# TEMPSENS.net
KiCad netlist of a schematic drawn in Altium Designer
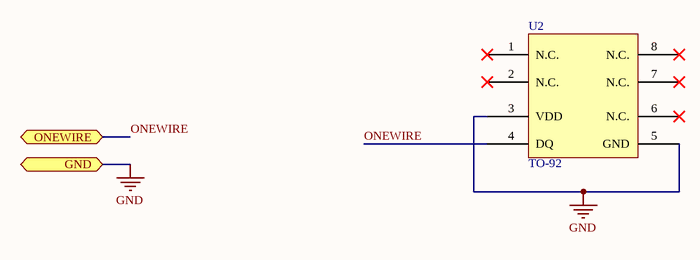
[diagram p0: TEMPSENS.SchDoc]

(export (version "E")
  (design (tool "Eeschema 10.0.6"))
  (components
    (comp (ref "U2")
      (value "TO-92")
      (footprint "DS18S20")
      (description "1-Wire Digital Thermometer")
      (fields (field (name "MANUFACTURER") "Maxim"))
      (libsource (lib "Tray 3 V2.0") (part "DS18S20"))
    )
  )
  (nets
    (net (code "1") (name "/ONEWIRE") (class "Default")
      (node (ref "U2") (pin "4") (pinfunction "DQ_4") (pintype "passive"))
    )
    (net (code "2") (name "GND") (class "Default")
      (node (ref "U2") (pin "3") (pinfunction "VDD_3") (pintype "passive"))
      (node (ref "U2") (pin "5") (pinfunction "GND_5") (pintype "passive"))
    )
    (net (code "3") (name "unconnected-(U2-N.C.-Pad1)") (class "Default")
      (node (ref "U2") (pin "1") (pinfunction "N.C._1") (pintype "passive+no_connect"))
    )
    (net (code "4") (name "unconnected-(U2-N.C.-Pad2)") (class "Default")
      (node (ref "U2") (pin "2") (pinfunction "N.C._2") (pintype "passive+no_connect"))
    )
    (net (code "5") (name "unconnected-(U2-N.C.-Pad6)") (class "Default")
      (node (ref "U2") (pin "6") (pinfunction "N.C._6") (pintype "passive+no_connect"))
    )
    (net (code "6") (name "unconnected-(U2-N.C.-Pad7)") (class "Default")
      (node (ref "U2") (pin "7") (pinfunction "N.C._7") (pintype "passive+no_connect"))
    )
    (net (code "7") (name "unconnected-(U2-N.C.-Pad8)") (class "Default")
      (node (ref "U2") (pin "8") (pinfunction "N.C._8") (pintype "passive+no_connect"))
    )
  )
)
